# HMS_8ValveDriver.net
KiCad netlist of a schematic drawn in EAGLE
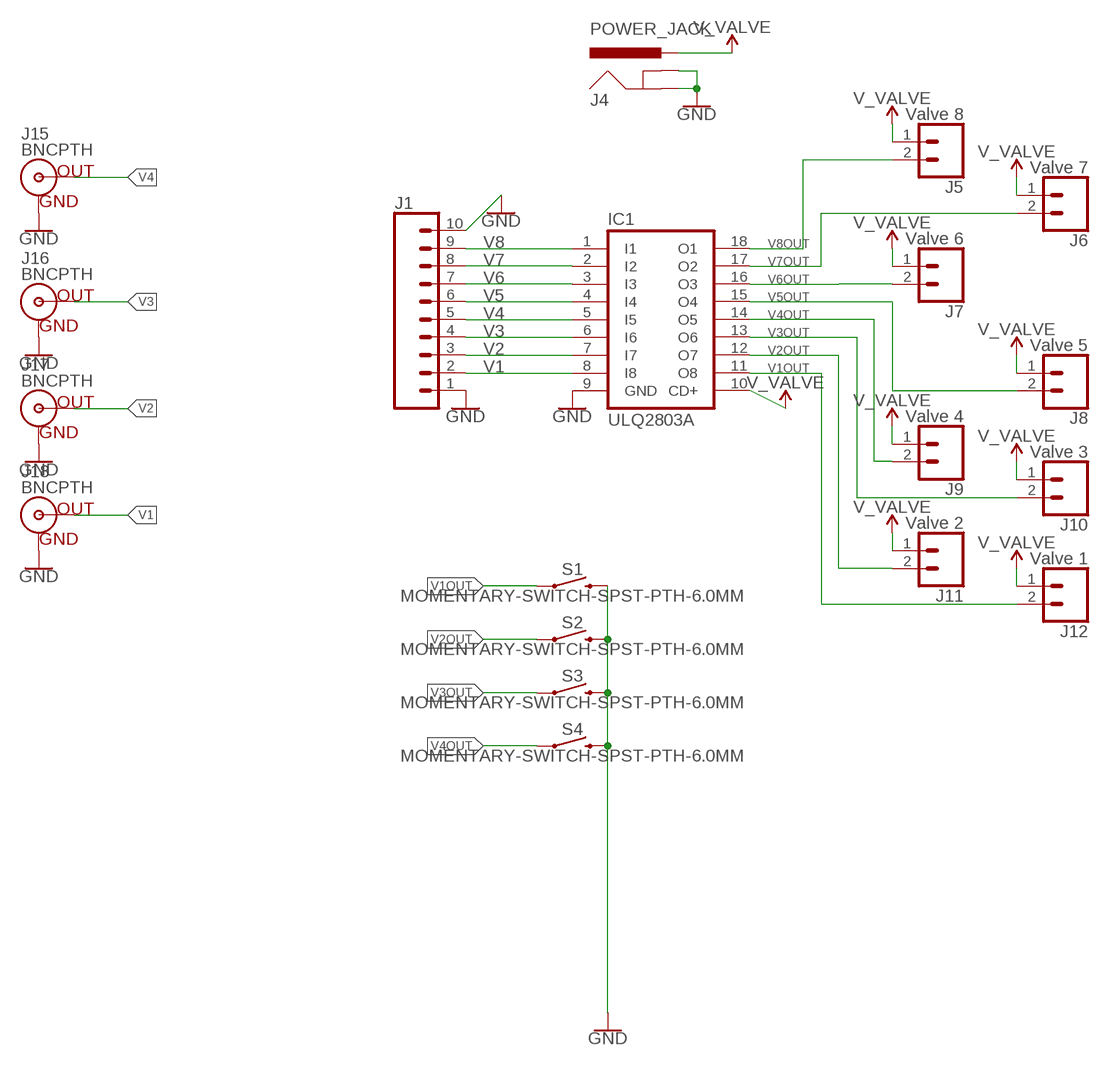
[diagram p0: schematic, sheet 1]

(export (version "E")
  (design (tool "Eeschema 10.0.6"))
  (components
    (comp (ref "IC1")
      (value "ULQ2803A")
      (footprint "eagle-import:DIL18")
      (libsource (lib "eagle-import") (part "ULN2803A"))
    )
    (comp (ref "J1")
      (value "CONN_10\"")
      (footprint "eagle-import:1X10")
      (libsource (lib "eagle-import") (part "CONN_10{dblquote}"))
    )
    (comp (ref "J4")
      (value "POWER_JACK")
      (footprint "eagle-import:POWER_JACK_PTH")
      (libsource (lib "eagle-import") (part "POWER_JACK"))
    )
    (comp (ref "J5")
      (value "Valve 8")
      (footprint "eagle-import:1X02")
      (libsource (lib "eagle-import") (part "CONN_02"))
    )
    (comp (ref "J6")
      (value "Valve 7")
      (footprint "eagle-import:1X02")
      (libsource (lib "eagle-import") (part "CONN_02"))
    )
    (comp (ref "J7")
      (value "Valve 6")
      (footprint "eagle-import:1X02")
      (libsource (lib "eagle-import") (part "CONN_02"))
    )
    (comp (ref "J8")
      (value "Valve 5")
      (footprint "eagle-import:1X02")
      (libsource (lib "eagle-import") (part "CONN_02"))
    )
    (comp (ref "J9")
      (value "Valve 4")
      (footprint "eagle-import:1X02")
      (libsource (lib "eagle-import") (part "CONN_02"))
    )
    (comp (ref "J10")
      (value "Valve 3")
      (footprint "eagle-import:1X02")
      (libsource (lib "eagle-import") (part "CONN_02"))
    )
    (comp (ref "J11")
      (value "Valve 2")
      (footprint "eagle-import:1X02")
      (libsource (lib "eagle-import") (part "CONN_02"))
    )
    (comp (ref "J12")
      (value "Valve 1")
      (footprint "eagle-import:1X02")
      (libsource (lib "eagle-import") (part "CONN_02"))
    )
    (comp (ref "J15")
      (value "BNCPTH")
      (footprint "eagle-import:BNC")
      (libsource (lib "eagle-import") (part "BNCPTH"))
    )
    (comp (ref "J16")
      (value "BNCPTH")
      (footprint "eagle-import:BNC")
      (libsource (lib "eagle-import") (part "BNCPTH"))
    )
    (comp (ref "J17")
      (value "BNCPTH")
      (footprint "eagle-import:BNC")
      (libsource (lib "eagle-import") (part "BNCPTH"))
    )
    (comp (ref "J18")
      (value "BNCPTH")
      (footprint "eagle-import:BNC")
      (libsource (lib "eagle-import") (part "BNCPTH"))
    )
    (comp (ref "S1")
      (value "MOMENTARY-SWITCH-SPST-PTH-6.0MM")
      (footprint "eagle-import:TACTILE_SWITCH_PTH_6.0MM")
      (libsource (lib "eagle-import") (part "MOMENTARY-SWITCH-SPST-PTH-6.0MM"))
    )
    (comp (ref "S2")
      (value "MOMENTARY-SWITCH-SPST-PTH-6.0MM")
      (footprint "eagle-import:TACTILE_SWITCH_PTH_6.0MM")
      (libsource (lib "eagle-import") (part "MOMENTARY-SWITCH-SPST-PTH-6.0MM"))
    )
    (comp (ref "S3")
      (value "MOMENTARY-SWITCH-SPST-PTH-6.0MM")
      (footprint "eagle-import:TACTILE_SWITCH_PTH_6.0MM")
      (libsource (lib "eagle-import") (part "MOMENTARY-SWITCH-SPST-PTH-6.0MM"))
    )
    (comp (ref "S4")
      (value "MOMENTARY-SWITCH-SPST-PTH-6.0MM")
      (footprint "eagle-import:TACTILE_SWITCH_PTH_6.0MM")
      (libsource (lib "eagle-import") (part "MOMENTARY-SWITCH-SPST-PTH-6.0MM"))
    )
  )
  (nets
    (net (code "1") (name "/V5") (class "Default")
      (node (ref "IC1") (pin "4") (pinfunction "I4_4") (pintype "input"))
      (node (ref "J1") (pin "6") (pinfunction "6_6") (pintype "passive"))
    )
    (net (code "2") (name "/V5OUT") (class "Default")
      (node (ref "IC1") (pin "15") (pinfunction "O4_15") (pintype "open_collector"))
      (node (ref "J8") (pin "2") (pinfunction "2_2") (pintype "passive"))
    )
    (net (code "3") (name "/V6") (class "Default")
      (node (ref "IC1") (pin "3") (pinfunction "I3_3") (pintype "input"))
      (node (ref "J1") (pin "7") (pinfunction "7_7") (pintype "passive"))
    )
    (net (code "4") (name "/V6OUT") (class "Default")
      (node (ref "IC1") (pin "16") (pinfunction "O3_16") (pintype "open_collector"))
      (node (ref "J7") (pin "2") (pinfunction "2_2") (pintype "passive"))
    )
    (net (code "5") (name "/V7") (class "Default")
      (node (ref "IC1") (pin "2") (pinfunction "I2_2") (pintype "input"))
      (node (ref "J1") (pin "8") (pinfunction "8_8") (pintype "passive"))
    )
    (net (code "6") (name "/V7OUT") (class "Default")
      (node (ref "IC1") (pin "17") (pinfunction "O2_17") (pintype "open_collector"))
      (node (ref "J6") (pin "2") (pinfunction "2_2") (pintype "passive"))
    )
    (net (code "7") (name "/V8") (class "Default")
      (node (ref "IC1") (pin "1") (pinfunction "I1_1") (pintype "input"))
      (node (ref "J1") (pin "9") (pinfunction "9_9") (pintype "passive"))
    )
    (net (code "8") (name "/V8OUT") (class "Default")
      (node (ref "IC1") (pin "18") (pinfunction "O1_18") (pintype "open_collector"))
      (node (ref "J5") (pin "2") (pinfunction "2_2") (pintype "passive"))
    )
    (net (code "9") (name "GND") (class "Default")
      (node (ref "IC1") (pin "9") (pinfunction "GND_9") (pintype "power_in"))
      (node (ref "J1") (pin "1") (pinfunction "1_1") (pintype "passive"))
      (node (ref "J1") (pin "10") (pinfunction "10_10") (pintype "passive"))
      (node (ref "J15") (pin "GND") (pinfunction "GND_GND") (pintype "bidirectional"))
      (node (ref "J16") (pin "GND") (pinfunction "GND_GND") (pintype "bidirectional"))
      (node (ref "J17") (pin "GND") (pinfunction "GND_GND") (pintype "bidirectional"))
      (node (ref "J18") (pin "GND") (pinfunction "GND_GND") (pintype "bidirectional"))
      (node (ref "J4") (pin "GND") (pinfunction "GND_GND") (pintype "bidirectional"))
      (node (ref "J4") (pin "GNDBREAK") (pinfunction "GNDBREAK_GNDBREAK") (pintype "bidirectional"))
      (node (ref "S1") (pin "3") (pinfunction "2_3") (pintype "passive"))
      (node (ref "S2") (pin "3") (pinfunction "2_3") (pintype "passive"))
      (node (ref "S3") (pin "3") (pinfunction "2_3") (pintype "passive"))
      (node (ref "S4") (pin "3") (pinfunction "2_3") (pintype "passive"))
    )
    (net (code "10") (name "V1") (class "Default")
      (node (ref "IC1") (pin "8") (pinfunction "I8_8") (pintype "input"))
      (node (ref "J1") (pin "2") (pinfunction "2_2") (pintype "passive"))
      (node (ref "J18") (pin "S") (pinfunction "OUT_S") (pintype "bidirectional"))
    )
    (net (code "11") (name "V1OUT") (class "Default")
      (node (ref "IC1") (pin "11") (pinfunction "O8_11") (pintype "open_collector"))
      (node (ref "J12") (pin "2") (pinfunction "2_2") (pintype "passive"))
      (node (ref "S1") (pin "1") (pinfunction "1_1") (pintype "passive"))
    )
    (net (code "12") (name "V2") (class "Default")
      (node (ref "IC1") (pin "7") (pinfunction "I7_7") (pintype "input"))
      (node (ref "J1") (pin "3") (pinfunction "3_3") (pintype "passive"))
      (node (ref "J17") (pin "S") (pinfunction "OUT_S") (pintype "bidirectional"))
    )
    (net (code "13") (name "V2OUT") (class "Default")
      (node (ref "IC1") (pin "12") (pinfunction "O7_12") (pintype "open_collector"))
      (node (ref "J11") (pin "2") (pinfunction "2_2") (pintype "passive"))
      (node (ref "S2") (pin "1") (pinfunction "1_1") (pintype "passive"))
    )
    (net (code "14") (name "V3") (class "Default")
      (node (ref "IC1") (pin "6") (pinfunction "I6_6") (pintype "input"))
      (node (ref "J1") (pin "4") (pinfunction "4_4") (pintype "passive"))
      (node (ref "J16") (pin "S") (pinfunction "OUT_S") (pintype "bidirectional"))
    )
    (net (code "15") (name "V3OUT") (class "Default")
      (node (ref "IC1") (pin "13") (pinfunction "O6_13") (pintype "open_collector"))
      (node (ref "J10") (pin "2") (pinfunction "2_2") (pintype "passive"))
      (node (ref "S3") (pin "1") (pinfunction "1_1") (pintype "passive"))
    )
    (net (code "16") (name "V4") (class "Default")
      (node (ref "IC1") (pin "5") (pinfunction "I5_5") (pintype "input"))
      (node (ref "J1") (pin "5") (pinfunction "5_5") (pintype "passive"))
      (node (ref "J15") (pin "S") (pinfunction "OUT_S") (pintype "bidirectional"))
    )
    (net (code "17") (name "V4OUT") (class "Default")
      (node (ref "IC1") (pin "14") (pinfunction "O5_14") (pintype "open_collector"))
      (node (ref "J9") (pin "2") (pinfunction "2_2") (pintype "passive"))
      (node (ref "S4") (pin "1") (pinfunction "1_1") (pintype "passive"))
    )
    (net (code "18") (name "V_VALVE") (class "Default")
      (node (ref "IC1") (pin "10") (pinfunction "CD+_10") (pintype "passive"))
      (node (ref "J10") (pin "1") (pinfunction "1_1") (pintype "passive"))
      (node (ref "J11") (pin "1") (pinfunction "1_1") (pintype "passive"))
      (node (ref "J12") (pin "1") (pinfunction "1_1") (pintype "passive"))
      (node (ref "J4") (pin "PWR") (pinfunction "PWR_PWR") (pintype "bidirectional"))
      (node (ref "J5") (pin "1") (pinfunction "1_1") (pintype "passive"))
      (node (ref "J6") (pin "1") (pinfunction "1_1") (pintype "passive"))
      (node (ref "J7") (pin "1") (pinfunction "1_1") (pintype "passive"))
      (node (ref "J8") (pin "1") (pinfunction "1_1") (pintype "passive"))
      (node (ref "J9") (pin "1") (pinfunction "1_1") (pintype "passive"))
    )
  )
)
